# BOOT_JTAG_AUX.net
KiCad netlist of a schematic drawn in Altium Designer
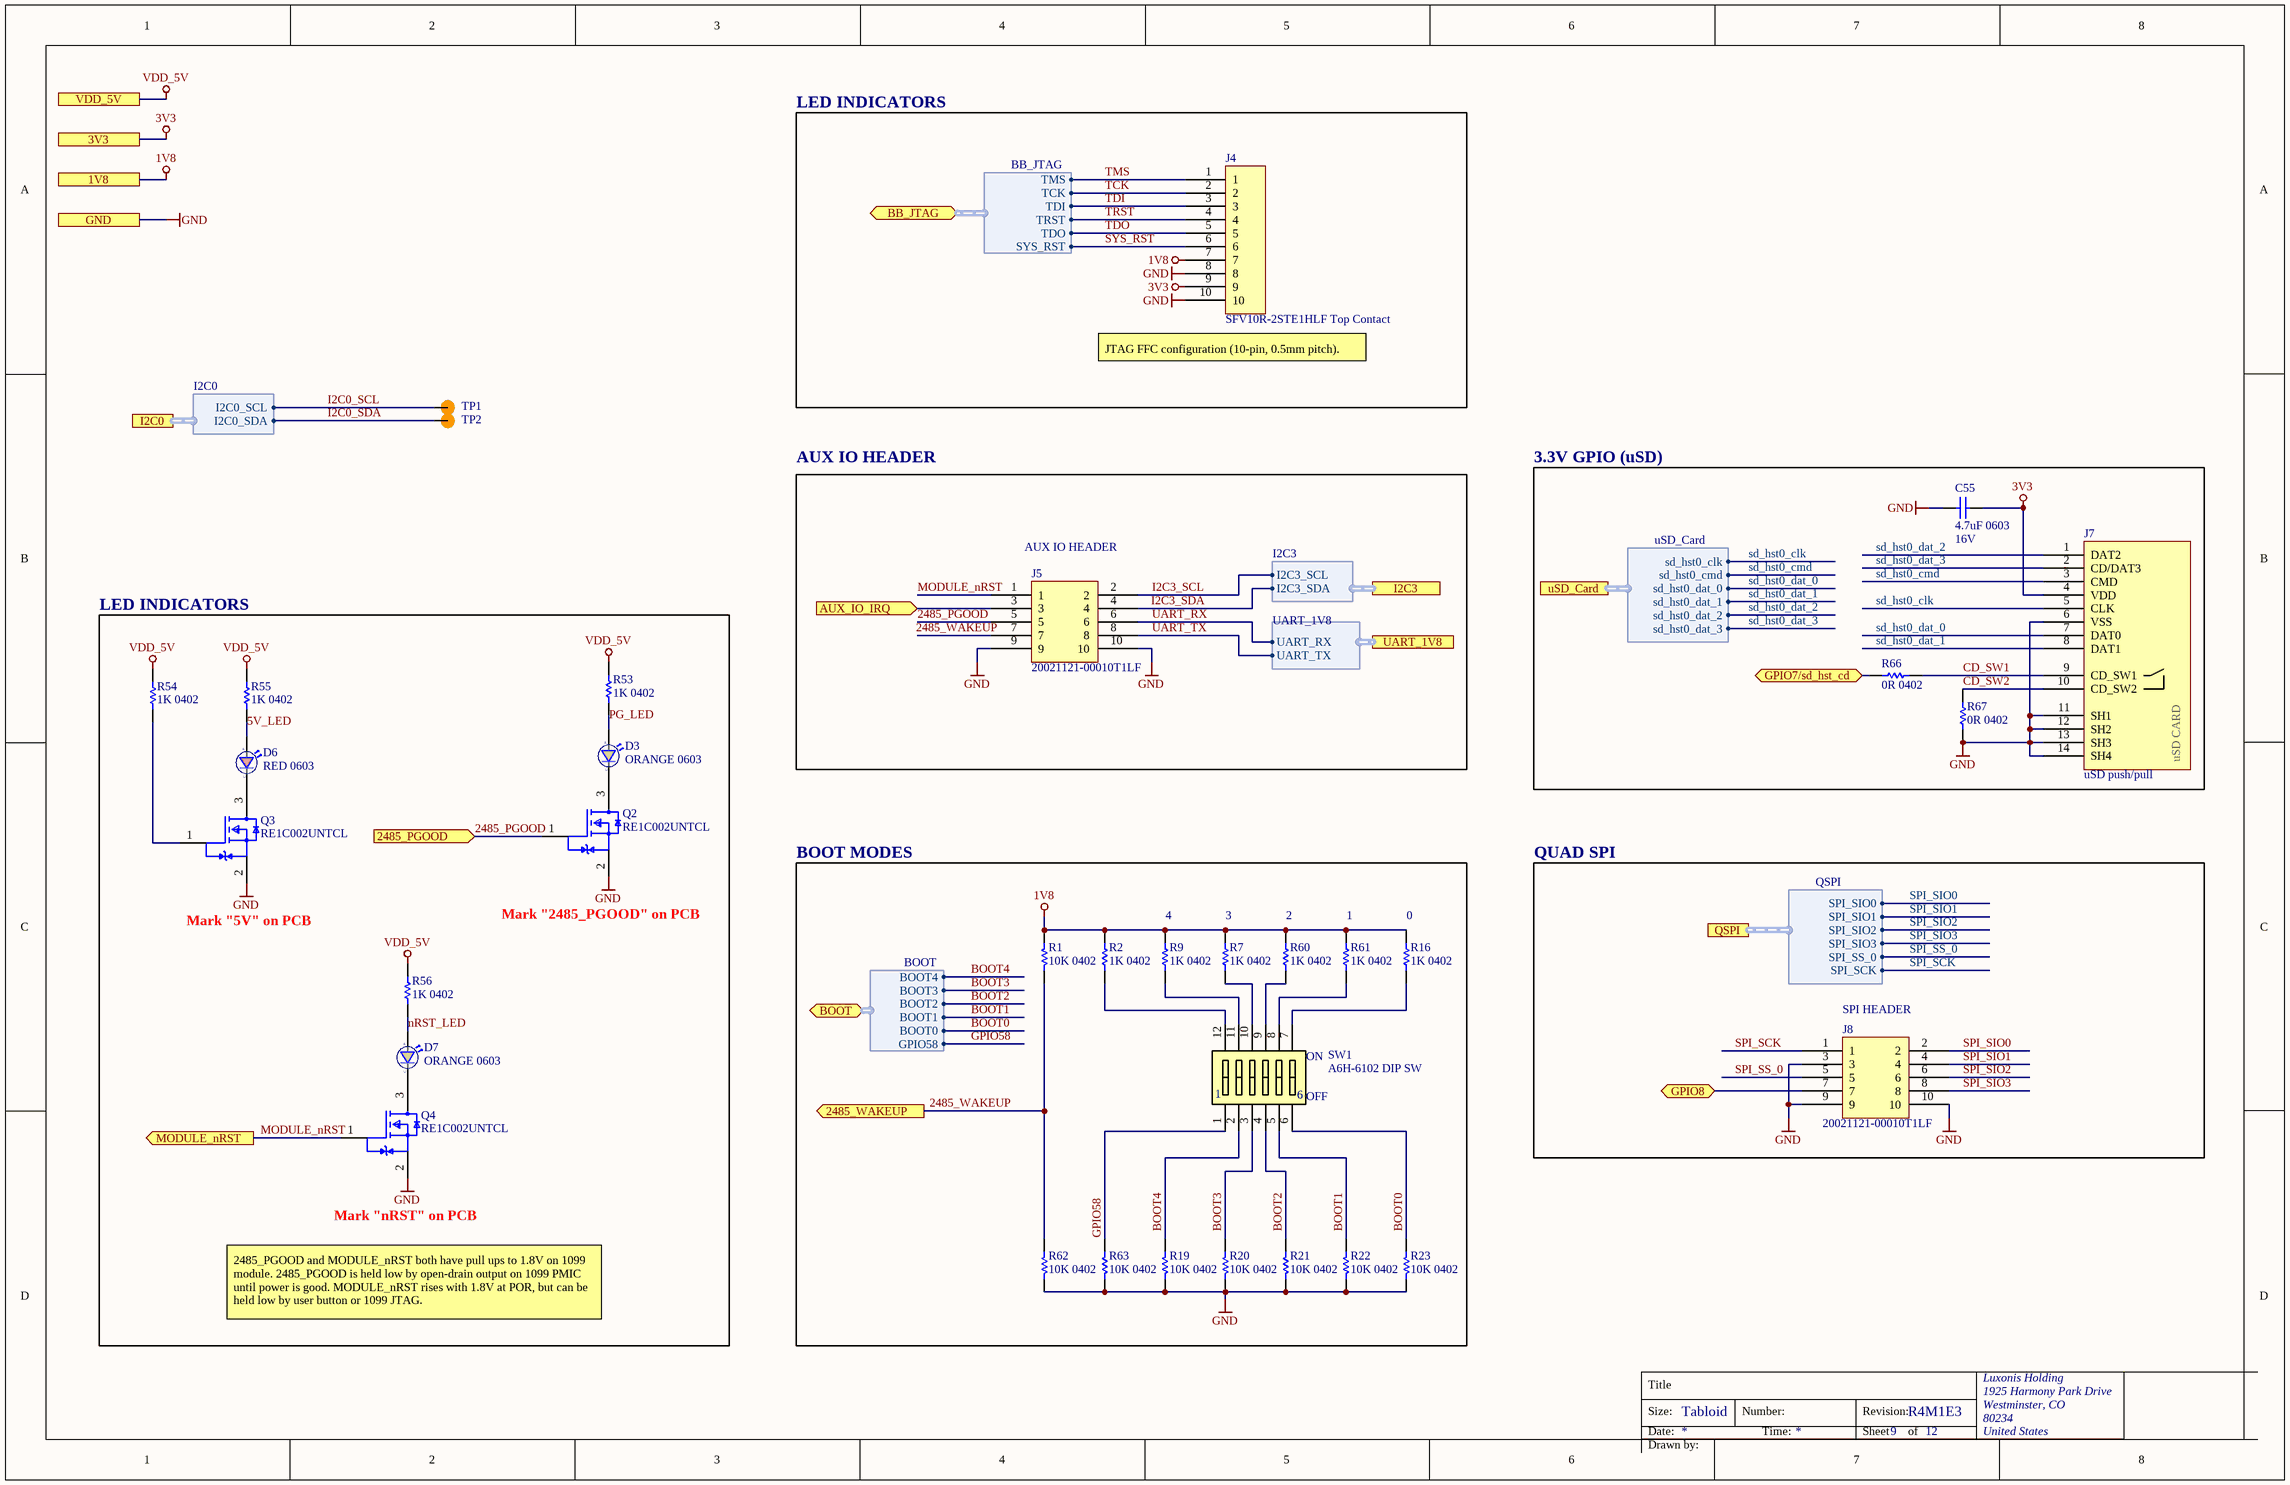
[diagram p0: BOOT_JTAG_AUX.SchDoc]

(export (version "E")
  (design (tool "Eeschema 10.0.6"))
  (components
    (comp (ref "C55")
      (value "4.7uF 0603")
      (footprint "CAP_Altium_Vault_Generic:CAPC0603(1608)100_N")
      (description "CAP CER 4.7UF 16V X5R 0603 10%")
      (fields (field (name "TOLERANCE") "10%") (field (name "VOLTAGE RATING") "16V"))
      (libsource (lib "LuxonisMaster") (part "GRM188R61C475KAAJD"))
    )
    (comp (ref "D3")
      (value "ORANGE 0603")
      (footprint "LuxonisMaster:SML_D1xx8W")
      (description "LED ORANGE DIFFUSED 0603 SMD Orange 605nm LED Indication - Discrete 2.2V 0603 (1608 Metric)")
      (libsource (lib "LuxonisMaster") (part "SML-D12D8WT86"))
    )
    (comp (ref "D6")
      (value "RED 0603")
      (footprint "LuxonisMaster:SML_D1xx8W")
      (description "LED RED DIFFUSED 0603 SMD Red 620nm LED Indication - Discrete 2.2V 0603 (1608 Metric)")
      (libsource (lib "LuxonisMaster") (part "SML-D12U8WT86"))
    )
    (comp (ref "D7")
      (value "ORANGE 0603")
      (footprint "LuxonisMaster:SML_D1xx8W")
      (description "LED ORANGE DIFFUSED 0603 SMD Orange 605nm LED Indication - Discrete 2.2V 0603 (1608 Metric)")
      (libsource (lib "LuxonisMaster") (part "SML-D12D8WT86"))
    )
    (comp (ref "J4")
      (value "SFV10R-2STE1HLF Top Contact")
      (footprint "LuxonisMaster:SFV10R-2STE1HLF")
      (description "CONN FFC TOP 10POS 0.50MM R/A")
      (libsource (lib "LuxonisMaster") (part "SFV10R-2STE1HLF"))
    )
    (comp (ref "J5")
      (value "20021121-00010T1LF")
      (footprint "LuxonisMaster:20021121-00010T1LF")
      (description "CONN HEADER SMD 10POS 1.27MM")
      (libsource (lib "LuxonisMaster") (part "20021121-00010T1LF"))
    )
    (comp (ref "J7")
      (value "uSD push/pull")
      (footprint "LuxonisMaster:104031-0811")
      (description "CONN MICRO SD CARD PUSH-PULL R/A")
      (libsource (lib "LuxonisMaster") (part "104031-0811"))
    )
    (comp (ref "J8")
      (value "20021121-00010T1LF")
      (footprint "LuxonisMaster:20021121-00010T1LF")
      (description "CONN HEADER SMD 10POS 1.27MM")
      (libsource (lib "LuxonisMaster") (part "20021121-00010T1LF"))
    )
    (comp (ref "Q2")
      (value "RE1C002UNTCL")
      (footprint "LuxonisMaster:RE1C002UNTCL")
      (description "MOSFET N-CH 20V 0.2A EMT3")
      (libsource (lib "LuxonisMaster") (part "RE1C002UNTCL"))
    )
    (comp (ref "Q3")
      (value "RE1C002UNTCL")
      (footprint "LuxonisMaster:RE1C002UNTCL")
      (description "MOSFET N-CH 20V 0.2A EMT3")
      (libsource (lib "LuxonisMaster") (part "RE1C002UNTCL"))
    )
    (comp (ref "Q4")
      (value "RE1C002UNTCL")
      (footprint "LuxonisMaster:RE1C002UNTCL")
      (description "MOSFET N-CH 20V 0.2A EMT3")
      (libsource (lib "LuxonisMaster") (part "RE1C002UNTCL"))
    )
    (comp (ref "R1")
      (value "10K 0402")
      (footprint "RES_Altium_Vault_Generic:RESC0402(1005)_N")
      (fields (field (name "TOLERANCE") "1%"))
      (libsource (lib "LuxonisMaster") (part "RC0402FR-1310KL"))
    )
    (comp (ref "R2")
      (value "1K 0402")
      (footprint "RES_Altium_Vault_Generic:RESC0402(1005)_N")
      (fields (field (name "TOLERANCE") "1%"))
      (libsource (lib "LuxonisMaster") (part "RC0402FR-071KL"))
    )
    (comp (ref "R7")
      (value "1K 0402")
      (footprint "RES_Altium_Vault_Generic:RESC0402(1005)_N")
      (fields (field (name "TOLERANCE") "1%"))
      (libsource (lib "LuxonisMaster") (part "RC0402FR-071KL"))
    )
    (comp (ref "R9")
      (value "1K 0402")
      (footprint "RES_Altium_Vault_Generic:RESC0402(1005)_N")
      (fields (field (name "TOLERANCE") "1%"))
      (libsource (lib "LuxonisMaster") (part "RC0402FR-071KL"))
    )
    (comp (ref "R16")
      (value "1K 0402")
      (footprint "RES_Altium_Vault_Generic:RESC0402(1005)_N")
      (fields (field (name "TOLERANCE") "1%"))
      (libsource (lib "LuxonisMaster") (part "RC0402FR-071KL"))
    )
    (comp (ref "R19")
      (value "10K 0402")
      (footprint "RES_Altium_Vault_Generic:RESC0402(1005)_N")
      (fields (field (name "TOLERANCE") "1%"))
      (libsource (lib "LuxonisMaster") (part "RC0402FR-1310KL"))
    )
    (comp (ref "R20")
      (value "10K 0402")
      (footprint "RES_Altium_Vault_Generic:RESC0402(1005)_N")
      (fields (field (name "TOLERANCE") "1%"))
      (libsource (lib "LuxonisMaster") (part "RC0402FR-1310KL"))
    )
    (comp (ref "R21")
      (value "10K 0402")
      (footprint "RES_Altium_Vault_Generic:RESC0402(1005)_N")
      (fields (field (name "TOLERANCE") "1%"))
      (libsource (lib "LuxonisMaster") (part "RC0402FR-1310KL"))
    )
    (comp (ref "R22")
      (value "10K 0402")
      (footprint "RES_Altium_Vault_Generic:RESC0402(1005)_N")
      (fields (field (name "TOLERANCE") "1%"))
      (libsource (lib "LuxonisMaster") (part "RC0402FR-1310KL"))
    )
    (comp (ref "R23")
      (value "10K 0402")
      (footprint "RES_Altium_Vault_Generic:RESC0402(1005)_N")
      (fields (field (name "TOLERANCE") "1%"))
      (libsource (lib "LuxonisMaster") (part "RC0402FR-1310KL"))
    )
    (comp (ref "R53")
      (value "1K 0402")
      (footprint "RES_Altium_Vault_Generic:RESC0402(1005)_N")
      (fields (field (name "TOLERANCE") "1%"))
      (libsource (lib "LuxonisMaster") (part "RC0402FR-071KL"))
    )
    (comp (ref "R54")
      (value "1K 0402")
      (footprint "RES_Altium_Vault_Generic:RESC0402(1005)_N")
      (fields (field (name "TOLERANCE") "1%"))
      (libsource (lib "LuxonisMaster") (part "RC0402FR-071KL"))
    )
    (comp (ref "R55")
      (value "1K 0402")
      (footprint "RES_Altium_Vault_Generic:RESC0402(1005)_N")
      (fields (field (name "TOLERANCE") "1%"))
      (libsource (lib "LuxonisMaster") (part "RC0402FR-071KL"))
    )
    (comp (ref "R56")
      (value "1K 0402")
      (footprint "RES_Altium_Vault_Generic:RESC0402(1005)_N")
      (fields (field (name "TOLERANCE") "1%"))
      (libsource (lib "LuxonisMaster") (part "RC0402FR-071KL"))
    )
    (comp (ref "R60")
      (value "1K 0402")
      (footprint "RES_Altium_Vault_Generic:RESC0402(1005)_N")
      (fields (field (name "TOLERANCE") "1%"))
      (libsource (lib "LuxonisMaster") (part "RC0402FR-071KL"))
    )
    (comp (ref "R61")
      (value "1K 0402")
      (footprint "RES_Altium_Vault_Generic:RESC0402(1005)_N")
      (fields (field (name "TOLERANCE") "1%"))
      (libsource (lib "LuxonisMaster") (part "RC0402FR-071KL"))
    )
    (comp (ref "R62")
      (value "10K 0402")
      (footprint "RES_Altium_Vault_Generic:RESC0402(1005)_N")
      (fields (field (name "TOLERANCE") "1%"))
      (libsource (lib "LuxonisMaster") (part "RC0402FR-1310KL"))
    )
    (comp (ref "R63")
      (value "10K 0402")
      (footprint "RES_Altium_Vault_Generic:RESC0402(1005)_N")
      (fields (field (name "TOLERANCE") "1%"))
      (libsource (lib "LuxonisMaster") (part "RC0402FR-1310KL"))
    )
    (comp (ref "R66")
      (value "0R 0402")
      (footprint "RES_Altium_Vault_Generic:RESC0402(1005)_N")
      (description "RES SMD 0 OHM JUMPER 1/16W 0402")
      (fields (field (name "TOLERANCE") "5%"))
      (libsource (lib "LuxonisMaster") (part "CRCW04020000Z0ED"))
    )
    (comp (ref "R67")
      (value "0R 0402")
      (footprint "RES_Altium_Vault_Generic:RESC0402(1005)_N")
      (description "RES SMD 0 OHM JUMPER 1/16W 0402")
      (fields (field (name "TOLERANCE") "5%"))
      (libsource (lib "LuxonisMaster") (part "CRCW04020000Z0ED"))
    )
    (comp (ref "SW1")
      (value "A6H-6102 DIP SW")
      (footprint "LuxonisMaster:A6H-610x")
      (description "SWITCH SLIDE DIP SPST 25MA 24V (SEALED)")
      (libsource (lib "LuxonisMaster") (part "A6H-6102"))
    )
    (comp (ref "TP1")
      (value "TP100_200_NS")
      (footprint "LuxonisMaster:TP100_200_NS")
      (libsource (lib "LuxonisMaster") (part "TEST_POINT"))
    )
    (comp (ref "TP2")
      (value "TP100_200_NS")
      (footprint "LuxonisMaster:TP100_200_NS")
      (libsource (lib "LuxonisMaster") (part "TEST_POINT"))
    )
  )
  (nets
    (net (code "8") (name "/5V_LED") (class "Default")
      (node (ref "D6") (pin "2") (pinfunction "A_2") (pintype "passive"))
      (node (ref "R55") (pin "1") (pinfunction "1_1") (pintype "passive"))
    )
    (net (code "9") (name "/2485_PGOOD") (class "Default")
      (node (ref "J5") (pin "5") (pinfunction "5_5") (pintype "passive"))
      (node (ref "Q2") (pin "1") (pinfunction "Gate_1") (pintype "passive"))
    )
    (net (code "10") (name "/2485_WAKEUP") (class "Default")
      (node (ref "R1") (pin "2") (pinfunction "2_2") (pintype "passive"))
      (node (ref "R62") (pin "1") (pinfunction "1_1") (pintype "passive"))
    )
    (net (code "11") (name "/AUX_IO_IRQ") (class "Default")
      (node (ref "J5") (pin "3") (pinfunction "3_3") (pintype "passive"))
    )
    (net (code "12") (name "/BOOT0") (class "Default")
      (node (ref "R23") (pin "1") (pinfunction "1_1") (pintype "passive"))
      (node (ref "SW1") (pin "6") (pinfunction "6_6") (pintype "passive"))
    )
    (net (code "13") (name "/BOOT1") (class "Default")
      (node (ref "R22") (pin "1") (pinfunction "1_1") (pintype "passive"))
      (node (ref "SW1") (pin "5") (pinfunction "5_5") (pintype "passive"))
    )
    (net (code "14") (name "/BOOT2") (class "Default")
      (node (ref "R21") (pin "1") (pinfunction "1_1") (pintype "passive"))
      (node (ref "SW1") (pin "4") (pinfunction "4_4") (pintype "passive"))
    )
    (net (code "15") (name "/BOOT3") (class "Default")
      (node (ref "R20") (pin "1") (pinfunction "1_1") (pintype "passive"))
      (node (ref "SW1") (pin "3") (pinfunction "3_3") (pintype "passive"))
    )
    (net (code "16") (name "/BOOT4") (class "Default")
      (node (ref "R19") (pin "1") (pinfunction "1_1") (pintype "passive"))
      (node (ref "SW1") (pin "2") (pinfunction "2_2") (pintype "passive"))
    )
    (net (code "17") (name "/CD_SW1") (class "Default")
      (node (ref "J7") (pin "9") (pinfunction "CD_SW1_9") (pintype "passive"))
      (node (ref "R66") (pin "1") (pinfunction "1_1") (pintype "passive"))
    )
    (net (code "18") (name "/CD_SW2") (class "Default")
      (node (ref "J7") (pin "10") (pinfunction "CD_SW2_10") (pintype "passive"))
      (node (ref "R67") (pin "2") (pinfunction "2_2") (pintype "passive"))
    )
    (net (code "19") (name "/GPIO7{slash}sd_hst_cd") (class "Default")
      (node (ref "R66") (pin "2") (pinfunction "2_2") (pintype "passive"))
    )
    (net (code "20") (name "/GPIO8") (class "Default")
      (node (ref "J8") (pin "7") (pinfunction "7_7") (pintype "passive"))
    )
    (net (code "21") (name "/GPIO58") (class "Default")
      (node (ref "R63") (pin "1") (pinfunction "1_1") (pintype "passive"))
      (node (ref "SW1") (pin "1") (pinfunction "1_1") (pintype "passive"))
    )
    (net (code "22") (name "/I2C0_SCL") (class "Default") (node (ref "TP1") (pin "1") (pintype "passive")))
    (net (code "23") (name "/I2C0_SDA") (class "Default") (node (ref "TP2") (pin "1") (pintype "passive")))
    (net (code "24") (name "/I2C3_SCL") (class "Default")
      (node (ref "J5") (pin "2") (pinfunction "2_2") (pintype "passive"))
    )
    (net (code "25") (name "/I2C3_SDA") (class "Default")
      (node (ref "J5") (pin "4") (pinfunction "4_4") (pintype "passive"))
    )
    (net (code "26") (name "/MODULE_nRST") (class "Default")
      (node (ref "J5") (pin "1") (pinfunction "1_1") (pintype "passive"))
      (node (ref "Q4") (pin "1") (pinfunction "Gate_1") (pintype "passive"))
    )
    (net (code "27") (name "/PG_LED") (class "Default")
      (node (ref "D3") (pin "2") (pinfunction "A_2") (pintype "passive"))
      (node (ref "R53") (pin "1") (pinfunction "1_1") (pintype "passive"))
    )
    (net (code "28") (name "/SPI_SCK") (class "Default")
      (node (ref "J8") (pin "1") (pinfunction "1_1") (pintype "passive"))
    )
    (net (code "29") (name "/SPI_SIO0") (class "Default")
      (node (ref "J8") (pin "2") (pinfunction "2_2") (pintype "passive"))
    )
    (net (code "30") (name "/SPI_SIO1") (class "Default")
      (node (ref "J8") (pin "4") (pinfunction "4_4") (pintype "passive"))
    )
    (net (code "31") (name "/SPI_SIO2") (class "Default")
      (node (ref "J8") (pin "6") (pinfunction "6_6") (pintype "passive"))
    )
    (net (code "32") (name "/SPI_SIO3") (class "Default")
      (node (ref "J8") (pin "8") (pinfunction "8_8") (pintype "passive"))
    )
    (net (code "33") (name "/SPI_SS_0") (class "Default")
      (node (ref "J8") (pin "5") (pinfunction "5_5") (pintype "passive"))
    )
    (net (code "34") (name "/SYS_RST") (class "Default")
      (node (ref "J4") (pin "6") (pinfunction "6_6") (pintype "passive"))
    )
    (net (code "35") (name "/TCK") (class "Default")
      (node (ref "J4") (pin "2") (pinfunction "2_2") (pintype "passive"))
    )
    (net (code "36") (name "/TDI") (class "Default")
      (node (ref "J4") (pin "3") (pinfunction "3_3") (pintype "passive"))
    )
    (net (code "37") (name "/TDO") (class "Default")
      (node (ref "J4") (pin "5") (pinfunction "5_5") (pintype "passive"))
    )
    (net (code "38") (name "/TMS") (class "Default")
      (node (ref "J4") (pin "1") (pinfunction "1_1") (pintype "passive"))
    )
    (net (code "39") (name "/TRST") (class "Default")
      (node (ref "J4") (pin "4") (pinfunction "4_4") (pintype "passive"))
    )
    (net (code "40") (name "/UART_RX") (class "Default")
      (node (ref "J5") (pin "6") (pinfunction "6_6") (pintype "passive"))
    )
    (net (code "41") (name "/UART_TX") (class "Default")
      (node (ref "J5") (pin "8") (pinfunction "8_8") (pintype "passive"))
    )
    (net (code "42") (name "/nRST_LED") (class "Default")
      (node (ref "D7") (pin "2") (pinfunction "A_2") (pintype "passive"))
      (node (ref "R56") (pin "1") (pinfunction "1_1") (pintype "passive"))
    )
    (net (code "43") (name "/sd_hst0_clk") (class "Default")
      (node (ref "J7") (pin "5") (pinfunction "CLK_5") (pintype "passive"))
    )
    (net (code "44") (name "/sd_hst0_cmd") (class "Default")
      (node (ref "J7") (pin "3") (pinfunction "CMD_3") (pintype "passive"))
    )
    (net (code "45") (name "/sd_hst0_dat_0") (class "Default")
      (node (ref "J7") (pin "7") (pinfunction "DAT0_7") (pintype "passive"))
    )
    (net (code "46") (name "/sd_hst0_dat_1") (class "Default")
      (node (ref "J7") (pin "8") (pinfunction "DAT1_8") (pintype "passive"))
    )
    (net (code "47") (name "/sd_hst0_dat_2") (class "Default")
      (node (ref "J7") (pin "1") (pinfunction "DAT2_1") (pintype "passive"))
    )
    (net (code "48") (name "/sd_hst0_dat_3") (class "Default")
      (node (ref "J7") (pin "2") (pinfunction "CD/DAT3_2") (pintype "passive"))
    )
    (net (code "56") (name "1V8") (class "Default")
      (node (ref "J4") (pin "7") (pinfunction "7_7") (pintype "passive"))
      (node (ref "R1") (pin "1") (pinfunction "1_1") (pintype "passive"))
      (node (ref "R16") (pin "2") (pinfunction "2_2") (pintype "passive"))
      (node (ref "R2") (pin "2") (pinfunction "2_2") (pintype "passive"))
      (node (ref "R60") (pin "2") (pinfunction "2_2") (pintype "passive"))
      (node (ref "R61") (pin "2") (pinfunction "2_2") (pintype "passive"))
      (node (ref "R7") (pin "2") (pinfunction "2_2") (pintype "passive"))
      (node (ref "R9") (pin "2") (pinfunction "2_2") (pintype "passive"))
    )
    (net (code "57") (name "3V3") (class "Default")
      (node (ref "C55") (pin "2") (pinfunction "2_2") (pintype "passive"))
      (node (ref "J4") (pin "9") (pinfunction "9_9") (pintype "passive"))
      (node (ref "J7") (pin "4") (pinfunction "VDD_4") (pintype "passive"))
    )
    (net (code "58") (name "GND") (class "Default")
      (node (ref "C55") (pin "1") (pinfunction "1_1") (pintype "passive"))
      (node (ref "J4") (pin "10") (pinfunction "10_10") (pintype "passive"))
      (node (ref "J4") (pin "8") (pinfunction "8_8") (pintype "passive"))
      (node (ref "J5") (pin "10") (pinfunction "10_10") (pintype "passive"))
      (node (ref "J5") (pin "9") (pinfunction "9_9") (pintype "passive"))
      (node (ref "J7") (pin "11") (pinfunction "SH1_11") (pintype "passive"))
      (node (ref "J7") (pin "12") (pinfunction "SH2_12") (pintype "passive"))
      (node (ref "J7") (pin "13") (pinfunction "SH3_13") (pintype "passive"))
      (node (ref "J7") (pin "14") (pinfunction "SH4_14") (pintype "passive"))
      (node (ref "J7") (pin "6") (pinfunction "VSS_6") (pintype "passive"))
      (node (ref "J8") (pin "10") (pinfunction "10_10") (pintype "passive"))
      (node (ref "J8") (pin "3") (pinfunction "3_3") (pintype "passive"))
      (node (ref "J8") (pin "9") (pinfunction "9_9") (pintype "passive"))
      (node (ref "Q2") (pin "2") (pinfunction "Source_2") (pintype "passive"))
      (node (ref "Q3") (pin "2") (pinfunction "Source_2") (pintype "passive"))
      (node (ref "Q4") (pin "2") (pinfunction "Source_2") (pintype "passive"))
      (node (ref "R19") (pin "2") (pinfunction "2_2") (pintype "passive"))
      (node (ref "R20") (pin "2") (pinfunction "2_2") (pintype "passive"))
      (node (ref "R21") (pin "2") (pinfunction "2_2") (pintype "passive"))
      (node (ref "R22") (pin "2") (pinfunction "2_2") (pintype "passive"))
      (node (ref "R23") (pin "2") (pinfunction "2_2") (pintype "passive"))
      (node (ref "R62") (pin "2") (pinfunction "2_2") (pintype "passive"))
      (node (ref "R63") (pin "2") (pinfunction "2_2") (pintype "passive"))
      (node (ref "R67") (pin "1") (pinfunction "1_1") (pintype "passive"))
    )
    (net (code "59") (name "Net-(D3-C)") (class "Default")
      (node (ref "D3") (pin "1") (pinfunction "C_1") (pintype "passive"))
      (node (ref "Q2") (pin "3") (pinfunction "Drain_3") (pintype "passive"))
    )
    (net (code "60") (name "Net-(D6-C)") (class "Default")
      (node (ref "D6") (pin "1") (pinfunction "C_1") (pintype "passive"))
      (node (ref "Q3") (pin "3") (pinfunction "Drain_3") (pintype "passive"))
    )
    (net (code "61") (name "Net-(D7-C)") (class "Default")
      (node (ref "D7") (pin "1") (pinfunction "C_1") (pintype "passive"))
      (node (ref "Q4") (pin "3") (pinfunction "Drain_3") (pintype "passive"))
    )
    (net (code "62") (name "Net-(Q3-Gate)") (class "Default")
      (node (ref "Q3") (pin "1") (pinfunction "Gate_1") (pintype "passive"))
      (node (ref "R54") (pin "1") (pinfunction "1_1") (pintype "passive"))
    )
    (net (code "63") (name "Net-(R2-Pad1)") (class "Default")
      (node (ref "R2") (pin "1") (pinfunction "1_1") (pintype "passive"))
      (node (ref "SW1") (pin "12") (pinfunction "12_12") (pintype "passive"))
    )
    (net (code "64") (name "Net-(R7-Pad1)") (class "Default")
      (node (ref "R7") (pin "1") (pinfunction "1_1") (pintype "passive"))
      (node (ref "SW1") (pin "10") (pinfunction "10_10") (pintype "passive"))
    )
    (net (code "65") (name "Net-(R9-Pad1)") (class "Default")
      (node (ref "R9") (pin "1") (pinfunction "1_1") (pintype "passive"))
      (node (ref "SW1") (pin "11") (pinfunction "11_11") (pintype "passive"))
    )
    (net (code "66") (name "Net-(R16-Pad1)") (class "Default")
      (node (ref "R16") (pin "1") (pinfunction "1_1") (pintype "passive"))
      (node (ref "SW1") (pin "7") (pinfunction "7_7") (pintype "passive"))
    )
    (net (code "67") (name "Net-(R60-Pad1)") (class "Default")
      (node (ref "R60") (pin "1") (pinfunction "1_1") (pintype "passive"))
      (node (ref "SW1") (pin "9") (pinfunction "9_9") (pintype "passive"))
    )
    (net (code "68") (name "Net-(R61-Pad1)") (class "Default")
      (node (ref "R61") (pin "1") (pinfunction "1_1") (pintype "passive"))
      (node (ref "SW1") (pin "8") (pinfunction "8_8") (pintype "passive"))
    )
    (net (code "69") (name "VDD_5V") (class "Default")
      (node (ref "R53") (pin "2") (pinfunction "2_2") (pintype "passive"))
      (node (ref "R54") (pin "2") (pinfunction "2_2") (pintype "passive"))
      (node (ref "R55") (pin "2") (pinfunction "2_2") (pintype "passive"))
      (node (ref "R56") (pin "2") (pinfunction "2_2") (pintype "passive"))
    )
    (net (code "70") (name "unconnected-(J5-Pad7)") (class "Default")
      (node (ref "J5") (pin "7") (pinfunction "7_7") (pintype "passive"))
    )
  )
)
